# MCU_nRF82532.net
KiCad netlist of a schematic drawn in Altium Designer
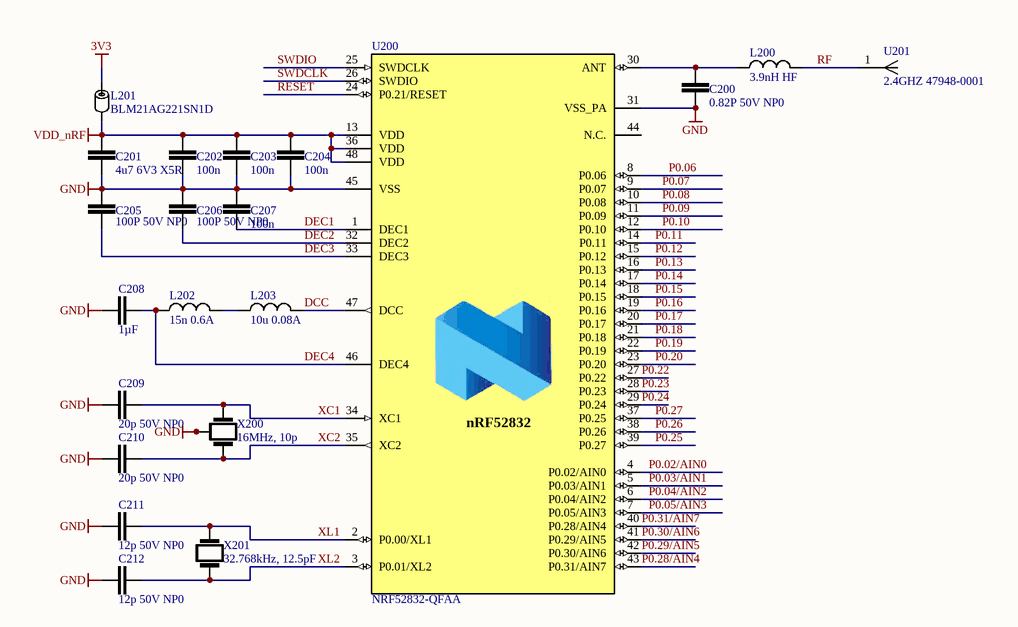
[diagram p0: MCU_nRF82532.SchDoc]

(export (version "E")
  (design (tool "Eeschema 10.0.6"))
  (components
    (comp (ref "C200")
      (value "0.82P 50V NP0")
      (footprint "CAPC1608N")
      (description "YAGEO (PHYCOMP) - CC0603CRNPO9BNR82 - CAP, MLCC, C0G/NP0, 0.82PF, 50V, 0603")
      (fields
        (field (name "MANUFACTURER PART NUMBER") "CC0603CRNPO9BNR82")
        (field (name "MANUFACTURER") "YAGEO (PHYCOMP)")
      )
      (libsource (lib "Discreete") (part "CAP 1608 0.82P 50V 5% NP0"))
    )
    (comp (ref "C201")
      (value "4u7 6V3 X5R")
      (footprint "CAPC2012N")
      (description "KEMET - C0805C475K9PACTU - CAP, MLCC, X5R, 4.7UF, 6.3V, 0805")
      (fields
        (field (name "MANUFACTURER PART NUMBER") "C0805C475K9PACTU")
        (field (name "MANUFACTURER") "KEMET")
      )
      (libsource (lib "Discreete") (part "CAP 2012 4U7F 6.3V 10% X5R"))
    )
    (comp (ref "C202")
      (value "100n")
      (footprint "CAPC2012N")
      (description "Ceramic Capacitor; Surface-Mount")
      (fields (field (name "TOLERANCE") "± 10%") (field (name "MANUFACTURER") "WALSIN"))
      (libsource (lib "Discreete") (part "CAP 2012 100N 25V 10% X7R"))
    )
    (comp (ref "C203")
      (value "100n")
      (footprint "CAPC2012N")
      (description "Ceramic Capacitor; Surface-Mount")
      (fields (field (name "TOLERANCE") "± 10%") (field (name "MANUFACTURER") "WALSIN"))
      (libsource (lib "Discreete") (part "CAP 2012 100N 25V 10% X7R"))
    )
    (comp (ref "C204")
      (value "100n")
      (footprint "CAPC2012N")
      (description "Ceramic Capacitor; Surface-Mount")
      (fields (field (name "TOLERANCE") "± 10%") (field (name "MANUFACTURER") "WALSIN"))
      (libsource (lib "Discreete") (part "CAP 2012 100N 25V 10% X7R"))
    )
    (comp (ref "C205")
      (value "100P 50V NP0")
      (footprint "CAPC2012N")
      (description "KEMET - C0805C101J5GACTU - CAP, MLCC, C0G/NP0, 100PF, 50V, 0805")
      (fields
        (field (name "MANUFACTURER") "KEMET")
        (field (name "MANUFACTURER PART NUMBER") "C0805C101J5GACTU")
      )
      (libsource (lib "Discreete") (part "CAP 2012 100P 50V 10% NP0"))
    )
    (comp (ref "C206")
      (value "100P 50V NP0")
      (footprint "CAPC2012N")
      (description "KEMET - C0805C101J5GACTU - CAP, MLCC, C0G/NP0, 100PF, 50V, 0805")
      (fields
        (field (name "MANUFACTURER") "KEMET")
        (field (name "MANUFACTURER PART NUMBER") "C0805C101J5GACTU")
      )
      (libsource (lib "Discreete") (part "CAP 2012 100P 50V 10% NP0"))
    )
    (comp (ref "C207")
      (value "100n")
      (footprint "CAPC2012N")
      (description "Ceramic Capacitor; Surface-Mount")
      (fields (field (name "TOLERANCE") "± 10%") (field (name "MANUFACTURER") "WALSIN"))
      (libsource (lib "") (part "CAP 2012 100N 25V 10% X7R_1"))
    )
    (comp (ref "C208")
      (value "1µF")
      (footprint "CAPC2012N")
      (description "CAP CER 1UF 25V X7R 0805")
      (fields
        (field (name "MANUFACTURER PART NUMBER") "GRM21BR71E105KA99L")
        (field (name "MANUFACTURER") "Murata Electronics North America")
      )
      (libsource (lib "Discreete") (part "CAP 2012 1U 25V 10% X7R"))
    )
    (comp (ref "C209")
      (value "20p 50V NP0")
      (footprint "CAPC2012N")
      (description "CAP CER 22PF 50V NP0 0805")
      (fields
        (field (name "MANUFACTURER PART NUMBER") "C0805C200J5GACTU")
        (field (name "MANUFACTURER") "KEMET")
      )
      (libsource (lib "Discreete") (part "CAP 2012 20P 50V 10% NP0"))
    )
    (comp (ref "C210")
      (value "20p 50V NP0")
      (footprint "CAPC2012N")
      (description "CAP CER 22PF 50V NP0 0805")
      (fields
        (field (name "MANUFACTURER PART NUMBER") "C0805C200J5GACTU")
        (field (name "MANUFACTURER") "KEMET")
      )
      (libsource (lib "Discreete") (part "CAP 2012 20P 50V 10% NP0"))
    )
    (comp (ref "C211")
      (value "12p 50V NP0")
      (footprint "CAPC2012N")
      (description "WALSIN - 0805N120J500CT - CAPACITOR, MLCC, NP0, 12PF, 50V, 0805")
      (fields
        (field (name "MANUFACTURER") "WALSIN")
        (field (name "MANUFACTURER PART NUMBER") "0805N120J500CT")
      )
      (libsource (lib "Discreete") (part "CAP 2012 12P 50V 10% NP0"))
    )
    (comp (ref "C212")
      (value "12p 50V NP0")
      (footprint "CAPC2012N")
      (description "WALSIN - 0805N120J500CT - CAPACITOR, MLCC, NP0, 12PF, 50V, 0805")
      (fields
        (field (name "MANUFACTURER") "WALSIN")
        (field (name "MANUFACTURER PART NUMBER") "0805N120J500CT")
      )
      (libsource (lib "Discreete") (part "CAP 2012 12P 50V 10% NP0"))
    )
    (comp (ref "L200")
      (value "3.9nH HF")
      (footprint "INDC2009N")
      (description "COILCRAFT - 0805HT-3N9TJLB - INDUCTOR, RF, 3.9NH, 5%, 6.1GHZ, SMD")
      (fields
        (field (name "MANUFACTURER PART NUMBER") "0805HT-3N9TJLB")
        (field (name "MANUFACTURER") "COILCRAFT")
      )
      (libsource (lib "Discreete") (part "IND 2012 3.9N 5% HF"))
    )
    (comp (ref "L201")
      (value "BLM21AG221SN1D")
      (footprint "INDC2009N")
      (description "MURATA - BLM21AG221SN1D - FERRITE BEAD, 0.13OHM, 800MA, 0805")
      (fields (field (name "MANUFACTURER") "MURATA"))
      (libsource (lib "Discreete") (part "IND 2012 FERRITE 220R @ 100MHz"))
    )
    (comp (ref "L202")
      (value "15n 0.6A")
      (footprint "INDP6060X32N")
      (description "VISHAY - IMC0805ER15NJ01 - HF INDUCTOR, 15NH, 600MA, 5% 3.6GHZ")
      (fields (field (name "TOLERANCE") "5%") (field (name "MANUFACTURER PART NUMBER") "IMC0805ER15NJ01"))
      (libsource (lib "Discreete") (part "IND 2012 15N 0.6A 5%"))
    )
    (comp (ref "L203")
      (value "10u 0.08A")
      (footprint "INDC2009N")
      (description "ISHAY - IMC0805ER100J01 - INDUCTOR, WIREWOUND, HIGH F")
      (fields (field (name "TOLERANCE") "5%") (field (name "MANUFACTURER PART NUMBER") "IMC0805ER100J01"))
      (libsource (lib "Discreete") (part "IND 2012 10U 0.08A 5%"))
    )
    (comp (ref "U200")
      (value "NRF52832-QFAA")
      (footprint "QFN40P600X600X90-48N")
      (description "Multi-protocol Bluetooth Low Energy, ANT and 2.4GHz proprietary system-on-chip")
      (fields
        (field (name "MANUFACTURER") "Nordic Semiconductor ASA")
        (field (name "MANUFACTURER PART NUMBER") "NRF52832-QFAA-R")
      )
      (libsource (lib "Integrated") (part "IC MCU nRF52832_QFAA ARM M0 BLUETOOTH"))
    )
    (comp (ref "U201")
      (value "2.4GHZ 47948-0001")
      (footprint "RF_ANT_CHIP_2.4GHZ_47948-0001")
      (libsource (lib "Discreete") (part "RF ANT CHIP 2.4GHZ 47948-0001"))
    )
    (comp (ref "X200")
      (value "16MHz, 10p")
      (footprint "SMD3225")
      (description "ABRACON - ABM10-16.000MHZ-D30-T3 - CRYSTAL, 16MHZ, 10PF, 2.5 X 2MM")
      (fields
        (field (name "MANUFACTURER") "ABRACON")
        (field (name "MANUFACTURER PART NUMBER") "ABM10-16.000MHZ-D30-T3")
      )
      (libsource (lib "Discreete") (part "XTAL SMD 16MHz 10P 20ppm"))
    )
    (comp (ref "X201")
      (value "32.768kHz, 12.5pF")
      (footprint "ABS06")
      (description "ABRACON - ABS06-32.768KHZ-T - CRYSTAL, 32.768KHZ, 12.5PF, SMD")
      (fields
        (field (name "MANUFACTURER PART NUMBER") "ABS06-32.768KHZ-T")
        (field (name "MANUFACTURER") "ABRACON")
      )
      (libsource (lib "Discreete") (part "XTAL SMD 32.768K 12.5P 20PPM"))
    )
  )
  (nets
    (net (code "1") (name "/DCC") (class "Default")
      (node (ref "L203") (pin "2") (pinfunction "2_2") (pintype "passive"))
      (node (ref "U200") (pin "47") (pinfunction "DCC_47") (pintype "output"))
    )
    (net (code "2") (name "/DEC1") (class "Default")
      (node (ref "C207") (pin "1") (pinfunction "1_1") (pintype "passive"))
      (node (ref "U200") (pin "1") (pinfunction "DEC1_1") (pintype "power_in"))
    )
    (net (code "3") (name "/DEC2") (class "Default")
      (node (ref "C206") (pin "1") (pinfunction "1_1") (pintype "passive"))
      (node (ref "U200") (pin "32") (pinfunction "DEC2_32") (pintype "power_in"))
    )
    (net (code "4") (name "/DEC3") (class "Default")
      (node (ref "C205") (pin "1") (pinfunction "1_1") (pintype "passive"))
      (node (ref "U200") (pin "33") (pinfunction "DEC3_33") (pintype "power_in"))
    )
    (net (code "5") (name "/DEC4") (class "Default")
      (node (ref "C208") (pin "2") (pinfunction "2_2") (pintype "passive"))
      (node (ref "L202") (pin "1") (pinfunction "1_1") (pintype "passive"))
      (node (ref "U200") (pin "46") (pinfunction "DEC4_46") (pintype "power_in"))
    )
    (net (code "6") (name "/P0.02{slash}AIN0") (class "Default")
      (node (ref "U200") (pin "4") (pinfunction "P0.02/AIN0_4") (pintype "bidirectional"))
    )
    (net (code "7") (name "/P0.03{slash}AIN1") (class "Default")
      (node (ref "U200") (pin "5") (pinfunction "P0.03/AIN1_5") (pintype "bidirectional"))
    )
    (net (code "8") (name "/P0.04{slash}AIN2") (class "Default")
      (node (ref "U200") (pin "6") (pinfunction "P0.04/AIN2_6") (pintype "bidirectional"))
    )
    (net (code "9") (name "/P0.05{slash}AIN3") (class "Default")
      (node (ref "U200") (pin "7") (pinfunction "P0.05/AIN3_7") (pintype "bidirectional"))
    )
    (net (code "10") (name "/P0.06") (class "Default")
      (node (ref "U200") (pin "8") (pinfunction "P0.06_8") (pintype "bidirectional"))
    )
    (net (code "11") (name "/P0.07") (class "Default")
      (node (ref "U200") (pin "9") (pinfunction "P0.07_9") (pintype "bidirectional"))
    )
    (net (code "12") (name "/P0.08") (class "Default")
      (node (ref "U200") (pin "10") (pinfunction "P0.08_10") (pintype "bidirectional"))
    )
    (net (code "13") (name "/P0.09") (class "Default")
      (node (ref "U200") (pin "11") (pinfunction "P0.09_11") (pintype "bidirectional"))
    )
    (net (code "14") (name "/P0.10") (class "Default")
      (node (ref "U200") (pin "12") (pinfunction "P0.10_12") (pintype "bidirectional"))
    )
    (net (code "15") (name "/P0.11") (class "Default")
      (node (ref "U200") (pin "14") (pinfunction "P0.11_14") (pintype "bidirectional"))
    )
    (net (code "16") (name "/P0.12") (class "Default")
      (node (ref "U200") (pin "15") (pinfunction "P0.12_15") (pintype "bidirectional"))
    )
    (net (code "17") (name "/P0.13") (class "Default")
      (node (ref "U200") (pin "16") (pinfunction "P0.13_16") (pintype "bidirectional"))
    )
    (net (code "18") (name "/P0.14") (class "Default")
      (node (ref "U200") (pin "17") (pinfunction "P0.14_17") (pintype "bidirectional"))
    )
    (net (code "19") (name "/P0.15") (class "Default")
      (node (ref "U200") (pin "18") (pinfunction "P0.15_18") (pintype "bidirectional"))
    )
    (net (code "20") (name "/P0.16") (class "Default")
      (node (ref "U200") (pin "19") (pinfunction "P0.16_19") (pintype "bidirectional"))
    )
    (net (code "21") (name "/P0.17") (class "Default")
      (node (ref "U200") (pin "20") (pinfunction "P0.17_20") (pintype "bidirectional"))
    )
    (net (code "22") (name "/P0.18") (class "Default")
      (node (ref "U200") (pin "21") (pinfunction "P0.18_21") (pintype "bidirectional"))
    )
    (net (code "23") (name "/P0.19") (class "Default")
      (node (ref "U200") (pin "22") (pinfunction "P0.19_22") (pintype "bidirectional"))
    )
    (net (code "24") (name "/P0.20") (class "Default")
      (node (ref "U200") (pin "23") (pinfunction "P0.20_23") (pintype "bidirectional"))
    )
    (net (code "25") (name "/P0.22") (class "Default")
      (node (ref "U200") (pin "27") (pinfunction "P0.22_27") (pintype "bidirectional"))
    )
    (net (code "26") (name "/P0.23") (class "Default")
      (node (ref "U200") (pin "28") (pinfunction "P0.23_28") (pintype "bidirectional"))
    )
    (net (code "27") (name "/P0.24") (class "Default")
      (node (ref "U200") (pin "29") (pinfunction "P0.24_29") (pintype "bidirectional"))
    )
    (net (code "28") (name "/P0.25") (class "Default")
      (node (ref "U200") (pin "39") (pinfunction "P0.27_39") (pintype "bidirectional"))
    )
    (net (code "29") (name "/P0.26") (class "Default")
      (node (ref "U200") (pin "38") (pinfunction "P0.26_38") (pintype "bidirectional"))
    )
    (net (code "30") (name "/P0.27") (class "Default")
      (node (ref "U200") (pin "37") (pinfunction "P0.25_37") (pintype "bidirectional"))
    )
    (net (code "31") (name "/P0.28{slash}AIN4") (class "Default")
      (node (ref "U200") (pin "43") (pinfunction "P0.31/AIN7_43") (pintype "bidirectional"))
    )
    (net (code "32") (name "/P0.29{slash}AIN5") (class "Default")
      (node (ref "U200") (pin "42") (pinfunction "P0.30/AIN6_42") (pintype "bidirectional"))
    )
    (net (code "33") (name "/P0.30{slash}AIN6") (class "Default")
      (node (ref "U200") (pin "41") (pinfunction "P0.29/AIN5_41") (pintype "bidirectional"))
    )
    (net (code "34") (name "/P0.31{slash}AIN7") (class "Default")
      (node (ref "U200") (pin "40") (pinfunction "P0.28/AIN4_40") (pintype "bidirectional"))
    )
    (net (code "35") (name "/RESET") (class "Default")
      (node (ref "U200") (pin "24") (pinfunction "P0.21/RESET_24") (pintype "bidirectional"))
    )
    (net (code "36") (name "/RF") (class "Default")
      (node (ref "L200") (pin "2") (pinfunction "2_2") (pintype "passive"))
      (node (ref "U201") (pin "1") (pinfunction "FT_1") (pintype "passive"))
    )
    (net (code "37") (name "/SWDCLK") (class "Default")
      (node (ref "U200") (pin "26") (pinfunction "SWDIO_26") (pintype "bidirectional"))
    )
    (net (code "38") (name "/SWDIO") (class "Default")
      (node (ref "U200") (pin "25") (pinfunction "SWDCLK_25") (pintype "input"))
    )
    (net (code "39") (name "/XC1") (class "Default")
      (node (ref "C209") (pin "2") (pinfunction "2_2") (pintype "passive"))
      (node (ref "U200") (pin "34") (pinfunction "XC1_34") (pintype "input"))
      (node (ref "X200") (pin "1") (pinfunction "1_1") (pintype "passive"))
    )
    (net (code "40") (name "/XC2") (class "Default")
      (node (ref "C210") (pin "2") (pinfunction "2_2") (pintype "passive"))
      (node (ref "U200") (pin "35") (pinfunction "XC2_35") (pintype "output"))
      (node (ref "X200") (pin "3") (pinfunction "3_3") (pintype "passive"))
    )
    (net (code "41") (name "/XL1") (class "Default")
      (node (ref "C211") (pin "1") (pinfunction "1_1") (pintype "passive"))
      (node (ref "U200") (pin "2") (pinfunction "P0.00/XL1_2") (pintype "bidirectional"))
      (node (ref "X201") (pin "2") (pinfunction "2_2") (pintype "passive"))
    )
    (net (code "42") (name "/XL2") (class "Default")
      (node (ref "C212") (pin "1") (pinfunction "1_1") (pintype "passive"))
      (node (ref "U200") (pin "3") (pinfunction "P0.01/XL2_3") (pintype "bidirectional"))
      (node (ref "X201") (pin "1") (pinfunction "1_1") (pintype "passive"))
    )
    (net (code "43") (name "3V3") (class "Default")
      (node (ref "L201") (pin "1") (pinfunction "1_1") (pintype "passive"))
    )
    (net (code "44") (name "GND") (class "Default")
      (node (ref "C200") (pin "1") (pinfunction "1_1") (pintype "passive"))
      (node (ref "C201") (pin "1") (pinfunction "1_1") (pintype "passive"))
      (node (ref "C202") (pin "2") (pinfunction "2_2") (pintype "passive"))
      (node (ref "C203") (pin "2") (pinfunction "2_2") (pintype "passive"))
      (node (ref "C204") (pin "2") (pinfunction "2_2") (pintype "passive"))
      (node (ref "C205") (pin "2") (pinfunction "2_2") (pintype "passive"))
      (node (ref "C206") (pin "2") (pinfunction "2_2") (pintype "passive"))
      (node (ref "C207") (pin "2") (pinfunction "2_2") (pintype "passive"))
      (node (ref "C208") (pin "1") (pinfunction "1_1") (pintype "passive"))
      (node (ref "C209") (pin "1") (pinfunction "1_1") (pintype "passive"))
      (node (ref "C210") (pin "1") (pinfunction "1_1") (pintype "passive"))
      (node (ref "C211") (pin "2") (pinfunction "2_2") (pintype "passive"))
      (node (ref "C212") (pin "2") (pinfunction "2_2") (pintype "passive"))
      (node (ref "U200") (pin "31") (pinfunction "VSS_PA_31") (pintype "power_in"))
      (node (ref "U200") (pin "45") (pinfunction "VSS_45") (pintype "power_in"))
      (node (ref "X200") (pin "2") (pinfunction "GND_2") (pintype "passive"))
      (node (ref "X200") (pin "4") (pinfunction "GND_4") (pintype "passive"))
    )
    (net (code "45") (name "Net-(L202-Pad2)") (class "Default")
      (node (ref "L202") (pin "2") (pinfunction "2_2") (pintype "passive"))
      (node (ref "L203") (pin "1") (pinfunction "1_1") (pintype "passive"))
    )
    (net (code "46") (name "Net-(U200-ANT)") (class "Default")
      (node (ref "C200") (pin "2") (pinfunction "2_2") (pintype "passive"))
      (node (ref "L200") (pin "1") (pinfunction "1_1") (pintype "passive"))
      (node (ref "U200") (pin "30") (pinfunction "ANT_30") (pintype "bidirectional"))
    )
    (net (code "47") (name "VDD_nRF") (class "Default")
      (node (ref "C201") (pin "2") (pinfunction "2_2") (pintype "passive"))
      (node (ref "C202") (pin "1") (pinfunction "1_1") (pintype "passive"))
      (node (ref "C203") (pin "1") (pinfunction "1_1") (pintype "passive"))
      (node (ref "C204") (pin "1") (pinfunction "1_1") (pintype "passive"))
      (node (ref "L201") (pin "2") (pinfunction "2_2") (pintype "passive"))
      (node (ref "U200") (pin "13") (pinfunction "VDD_13") (pintype "power_in"))
      (node (ref "U200") (pin "36") (pinfunction "VDD_36") (pintype "power_in"))
      (node (ref "U200") (pin "48") (pinfunction "VDD_48") (pintype "power_in"))
    )
    (net (code "48") (name "unconnected-(U200-N.C.-Pad44)") (class "Default")
      (node (ref "U200") (pin "44") (pinfunction "N.C._44") (pintype "power_in"))
    )
  )
)
